# 05021002_Serial.net
KiCad netlist of a schematic drawn in Altium Designer
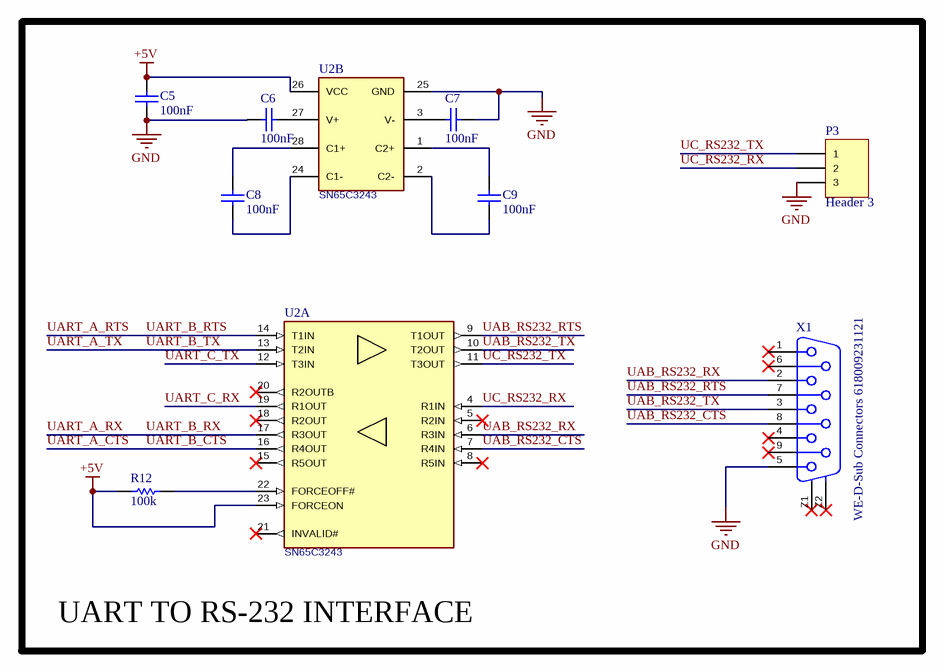
[diagram p0: 05021002_Serial.SchDoc]

(export (version "E")
  (design (tool "Eeschema 10.0.6"))
  (components
    (comp (ref "C5")
      (value "100nF")
      (footprint "CAPC2012X135N")
      (description "Generic Capacitor")
      (libsource (lib "capacitor_smd_gen") (part "capacitor_gen"))
    )
    (comp (ref "C6")
      (value "100nF")
      (footprint "CAPC2012X135N")
      (description "Generic Capacitor")
      (libsource (lib "capacitor_smd_gen") (part "capacitor_gen"))
    )
    (comp (ref "C7")
      (value "100nF")
      (footprint "CAPC2012X135N")
      (description "Generic Capacitor")
      (libsource (lib "capacitor_smd_gen") (part "capacitor_gen"))
    )
    (comp (ref "C8")
      (value "100nF")
      (footprint "CAPC2012X135N")
      (description "Generic Capacitor")
      (libsource (lib "capacitor_smd_gen") (part "capacitor_gen"))
    )
    (comp (ref "C9")
      (value "100nF")
      (footprint "CAPC2012X135N")
      (description "Generic Capacitor")
      (libsource (lib "capacitor_smd_gen") (part "capacitor_gen"))
    )
    (comp (ref "P3")
      (value "Header 3")
      (footprint "HDR1X3")
      (description "Header, 3-Pin")
      (fields (field (name "PUBLISHER") "Altium Limited"))
      (libsource (lib "Miscellaneous Connectors") (part "Header 3"))
    )
    (comp (ref "R12")
      (value "100k")
      (footprint "0805")
      (libsource (lib "resistor_smd_gen") (part "resistor_gen"))
    )
    (comp (ref "U2")
      (value "SN65C3243")
      (footprint "SOP65P780X200-28N")
      (description "RS-232 Serial Transceiver")
      (fields (field (name "PART NUMBER 1") "SN65C3243"))
      (libsource (lib "Evaluation Board") (part "IC-TI-SN65C3243"))
    )
    (comp (ref "X1")
      (value "WE-D-Sub Connectors 618009231121")
      (footprint "618009231121")
      (description "WR-DSUB Female Angled PCB Connector")
      (fields (field (name "CREATED BY") "Karrer Zheng"))
      (libsource (lib "Altium_WR-DSUB_rev15a") (part "WE-D-Sub Connectors 618009231121"))
    )
  )
  (nets
    (net (code "1") (name "+5V") (class "Default")
      (node (ref "C5") (pin "2") (pinfunction "2_2") (pintype "passive"))
      (node (ref "R12") (pin "1") (pinfunction "1_1") (pintype "passive"))
      (node (ref "U2") (pin "23") (pinfunction "FORCEON_23") (pintype "input"))
      (node (ref "U2") (pin "26") (pinfunction "VCC_26") (pintype "power_in"))
    )
    (net (code "2") (name "/UAB_RS232_CTS") (class "Default")
      (node (ref "U2") (pin "7") (pinfunction "R4IN_7") (pintype "input"))
      (node (ref "X1") (pin "8") (pinfunction "8_8") (pintype "passive"))
    )
    (net (code "3") (name "/UAB_RS232_RTS") (class "Default")
      (node (ref "U2") (pin "9") (pinfunction "T1OUT_9") (pintype "output"))
      (node (ref "X1") (pin "7") (pinfunction "7_7") (pintype "passive"))
    )
    (net (code "4") (name "/UAB_RS232_RX") (class "Default")
      (node (ref "U2") (pin "6") (pinfunction "R3IN_6") (pintype "input"))
      (node (ref "X1") (pin "2") (pinfunction "2_2") (pintype "passive"))
    )
    (net (code "5") (name "/UAB_RS232_TX") (class "Default")
      (node (ref "U2") (pin "10") (pinfunction "T2OUT_10") (pintype "output"))
      (node (ref "X1") (pin "3") (pinfunction "3_3") (pintype "passive"))
    )
    (net (code "6") (name "/UART_A_CTS") (class "Default")
      (node (ref "U2") (pin "16") (pinfunction "R4OUT_16") (pintype "output"))
    )
    (net (code "7") (name "/UART_A_RTS") (class "Default")
      (node (ref "U2") (pin "14") (pinfunction "T1IN_14") (pintype "input"))
    )
    (net (code "8") (name "/UART_A_RX") (class "Default")
      (node (ref "U2") (pin "17") (pinfunction "R3OUT_17") (pintype "output"))
    )
    (net (code "9") (name "/UART_A_TX") (class "Default")
      (node (ref "U2") (pin "13") (pinfunction "T2IN_13") (pintype "input"))
    )
    (net (code "10") (name "/UART_C_RX") (class "Default")
      (node (ref "U2") (pin "19") (pinfunction "R1OUT_19") (pintype "output"))
    )
    (net (code "11") (name "/UART_C_TX") (class "Default")
      (node (ref "U2") (pin "12") (pinfunction "T3IN_12") (pintype "input"))
    )
    (net (code "12") (name "/UC_RS232_RX") (class "Default")
      (node (ref "P3") (pin "2") (pinfunction "2_2") (pintype "passive"))
      (node (ref "U2") (pin "4") (pinfunction "R1IN_4") (pintype "input"))
    )
    (net (code "13") (name "/UC_RS232_TX") (class "Default")
      (node (ref "P3") (pin "1") (pinfunction "1_1") (pintype "passive"))
      (node (ref "U2") (pin "11") (pinfunction "T3OUT_11") (pintype "output"))
    )
    (net (code "14") (name "GND") (class "Default")
      (node (ref "C5") (pin "1") (pinfunction "1_1") (pintype "passive"))
      (node (ref "C6") (pin "1") (pinfunction "1_1") (pintype "passive"))
      (node (ref "C7") (pin "2") (pinfunction "2_2") (pintype "passive"))
      (node (ref "P3") (pin "3") (pinfunction "3_3") (pintype "passive"))
      (node (ref "U2") (pin "25") (pinfunction "GND_25") (pintype "power_in"))
      (node (ref "X1") (pin "5") (pinfunction "5_5") (pintype "passive"))
    )
    (net (code "15") (name "Net-(U2A-FORCEOFF#)") (class "Default")
      (node (ref "R12") (pin "2") (pinfunction "2_2") (pintype "passive"))
      (node (ref "U2") (pin "22") (pinfunction "FORCEOFF#_22") (pintype "input"))
    )
    (net (code "16") (name "Net-(U2B-C1+)") (class "Default")
      (node (ref "C8") (pin "2") (pinfunction "2_2") (pintype "passive"))
      (node (ref "U2") (pin "28") (pinfunction "C1+_28") (pintype "power_in"))
    )
    (net (code "17") (name "Net-(U2B-C1-)") (class "Default")
      (node (ref "C8") (pin "1") (pinfunction "1_1") (pintype "passive"))
      (node (ref "U2") (pin "24") (pinfunction "C1-_24") (pintype "power_in"))
    )
    (net (code "18") (name "Net-(U2B-C2+)") (class "Default")
      (node (ref "C9") (pin "2") (pinfunction "2_2") (pintype "passive"))
      (node (ref "U2") (pin "1") (pinfunction "C2+_1") (pintype "power_in"))
    )
    (net (code "19") (name "Net-(U2B-C2-)") (class "Default")
      (node (ref "C9") (pin "1") (pinfunction "1_1") (pintype "passive"))
      (node (ref "U2") (pin "2") (pinfunction "C2-_2") (pintype "power_in"))
    )
    (net (code "20") (name "Net-(U2B-V+)") (class "Default")
      (node (ref "C6") (pin "2") (pinfunction "2_2") (pintype "passive"))
      (node (ref "U2") (pin "27") (pinfunction "V+_27") (pintype "power_in"))
    )
    (net (code "21") (name "Net-(U2B-V-)") (class "Default")
      (node (ref "C7") (pin "1") (pinfunction "1_1") (pintype "passive"))
      (node (ref "U2") (pin "3") (pinfunction "V-_3") (pintype "power_in"))
    )
    (net (code "22") (name "unconnected-(U2A-INVALID#-Pad21)") (class "Default")
      (node (ref "U2") (pin "21") (pinfunction "INVALID#_21") (pintype "output+no_connect"))
    )
    (net (code "23") (name "unconnected-(U2A-R2IN-Pad5)") (class "Default")
      (node (ref "U2") (pin "5") (pinfunction "R2IN_5") (pintype "input+no_connect"))
    )
    (net (code "24") (name "unconnected-(U2A-R2OUT-Pad18)") (class "Default")
      (node (ref "U2") (pin "18") (pinfunction "R2OUT_18") (pintype "output+no_connect"))
    )
    (net (code "25") (name "unconnected-(U2A-R2OUTB-Pad20)") (class "Default")
      (node (ref "U2") (pin "20") (pinfunction "R2OUTB_20") (pintype "output+no_connect"))
    )
    (net (code "26") (name "unconnected-(U2A-R5IN-Pad8)") (class "Default")
      (node (ref "U2") (pin "8") (pinfunction "R5IN_8") (pintype "input+no_connect"))
    )
    (net (code "27") (name "unconnected-(U2A-R5OUT-Pad15)") (class "Default")
      (node (ref "U2") (pin "15") (pinfunction "R5OUT_15") (pintype "output+no_connect"))
    )
    (net (code "28") (name "unconnected-(X1-GND-PadZ1)") (class "Default")
      (node (ref "X1") (pin "Z1") (pinfunction "GND_Z1") (pintype "passive+no_connect"))
    )
    (net (code "29") (name "unconnected-(X1-GND-PadZ2)") (class "Default")
      (node (ref "X1") (pin "Z2") (pinfunction "GND_Z2") (pintype "passive+no_connect"))
    )
    (net (code "30") (name "unconnected-(X1-Pad1)") (class "Default")
      (node (ref "X1") (pin "1") (pinfunction "1_1") (pintype "passive+no_connect"))
    )
    (net (code "31") (name "unconnected-(X1-Pad4)") (class "Default")
      (node (ref "X1") (pin "4") (pinfunction "4_4") (pintype "passive+no_connect"))
    )
    (net (code "32") (name "unconnected-(X1-Pad6)") (class "Default")
      (node (ref "X1") (pin "6") (pinfunction "6_6") (pintype "passive+no_connect"))
    )
    (net (code "33") (name "unconnected-(X1-Pad9)") (class "Default")
      (node (ref "X1") (pin "9") (pinfunction "9_9") (pintype "passive+no_connect"))
    )
  )
)
